# CAN-D_Rev1.net
KiCad netlist of a schematic drawn in EAGLE
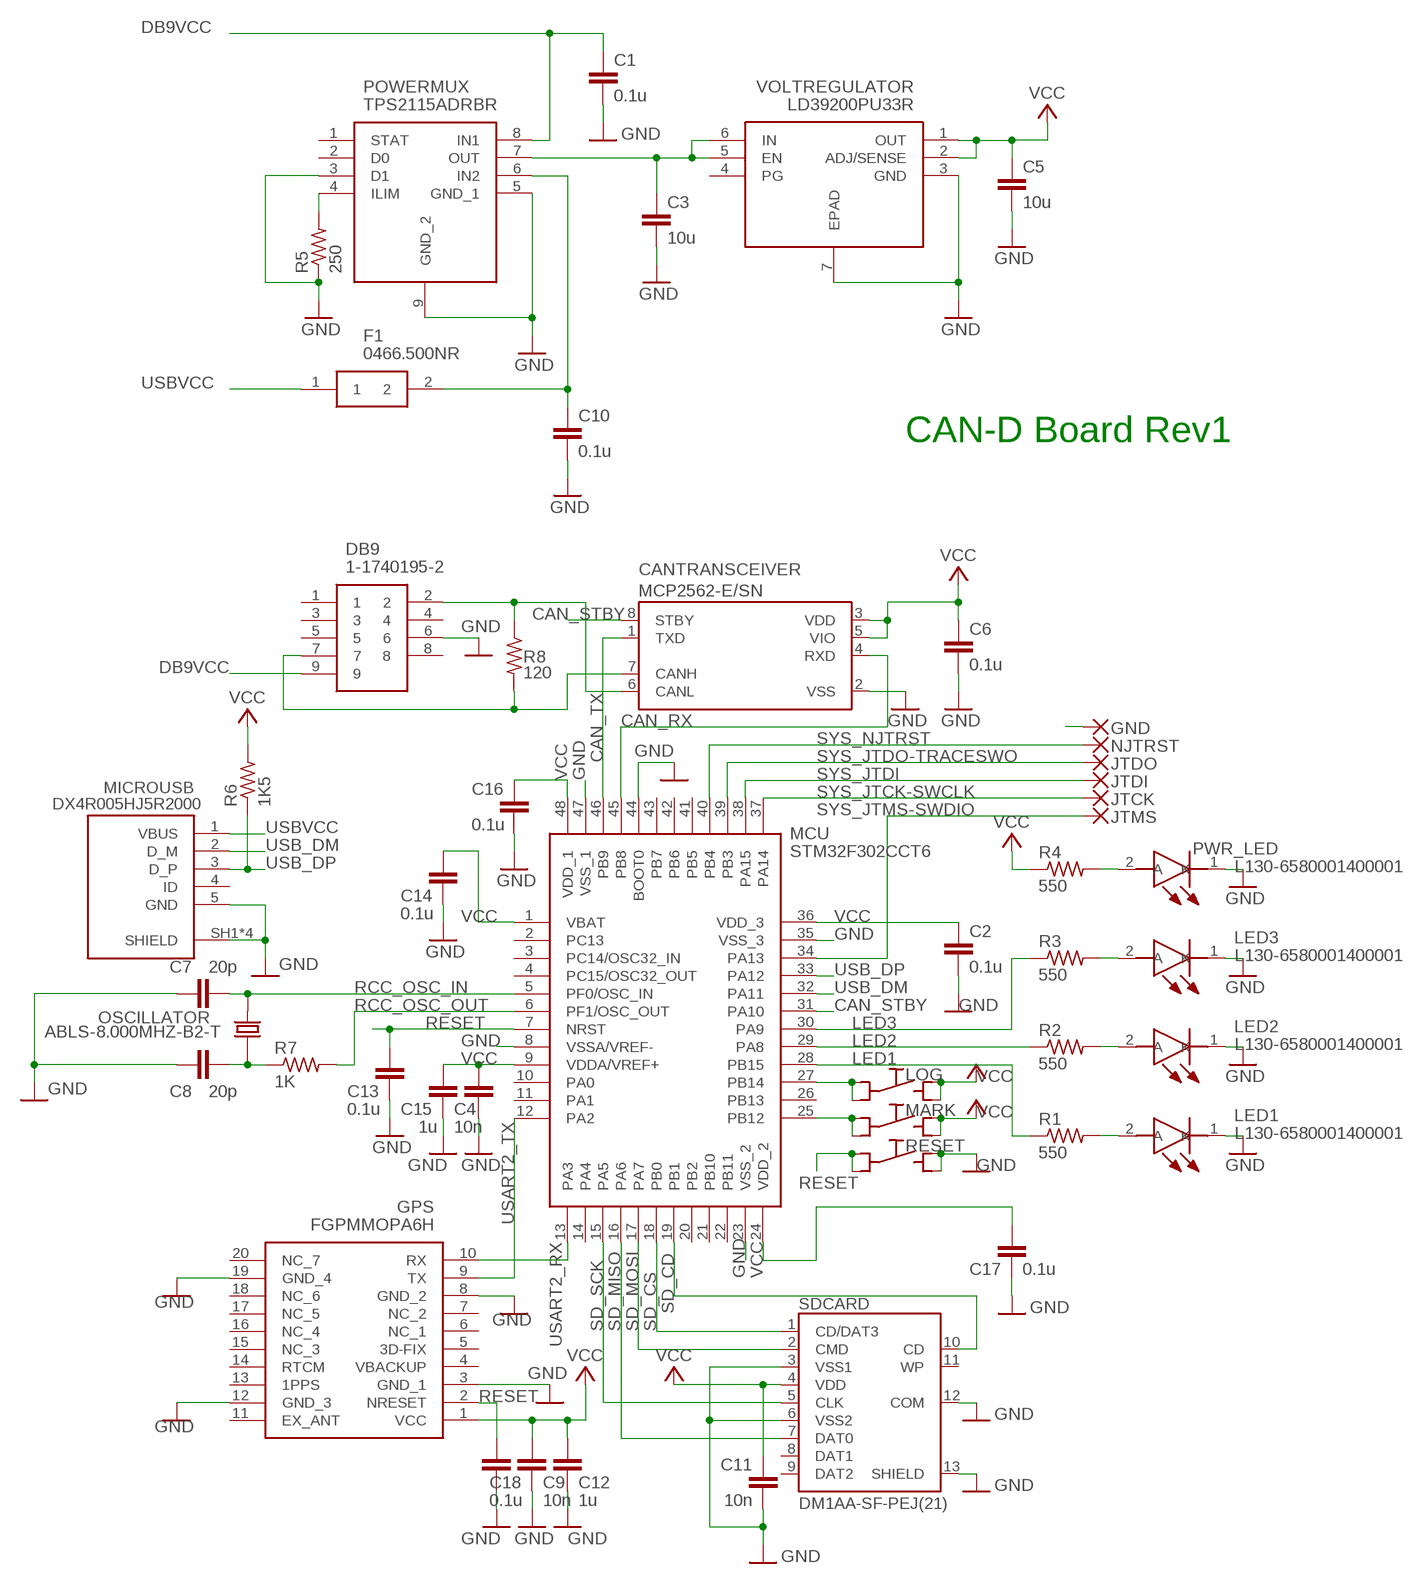
[diagram p0: schematic, sheet 1]

(export (version "E")
  (design (tool "Eeschema 10.0.6"))
  (components
    (comp (ref "C1")
      (value "0.1u")
      (footprint "eagle-import:C0603")
      (libsource (lib "eagle-import") (part "C-EUC0603"))
    )
    (comp (ref "C2")
      (value "0.1u")
      (footprint "eagle-import:C0603")
      (libsource (lib "eagle-import") (part "C-EUC0603"))
    )
    (comp (ref "C3")
      (value "10u")
      (footprint "eagle-import:C0603")
      (libsource (lib "eagle-import") (part "C-EUC0603"))
    )
    (comp (ref "C4")
      (value "10n")
      (footprint "eagle-import:C0603")
      (libsource (lib "eagle-import") (part "C-EUC0603"))
    )
    (comp (ref "C5")
      (value "10u")
      (footprint "eagle-import:C0603")
      (libsource (lib "eagle-import") (part "C-EUC0603"))
    )
    (comp (ref "C6")
      (value "0.1u")
      (footprint "eagle-import:C0603")
      (libsource (lib "eagle-import") (part "C-EUC0603"))
    )
    (comp (ref "C7")
      (value "20p")
      (footprint "eagle-import:C0603")
      (libsource (lib "eagle-import") (part "C-EUC0603"))
    )
    (comp (ref "C8")
      (value "20p")
      (footprint "eagle-import:C0603")
      (libsource (lib "eagle-import") (part "C-EUC0603"))
    )
    (comp (ref "C9")
      (value "10n")
      (footprint "eagle-import:C0603")
      (libsource (lib "eagle-import") (part "C-EUC0603"))
    )
    (comp (ref "C10")
      (value "0.1u")
      (footprint "eagle-import:C0603")
      (libsource (lib "eagle-import") (part "C-EUC0603"))
    )
    (comp (ref "C11")
      (value "10n")
      (footprint "eagle-import:C0603")
      (libsource (lib "eagle-import") (part "C-EUC0603"))
    )
    (comp (ref "C12")
      (value "1u")
      (footprint "eagle-import:C0603")
      (libsource (lib "eagle-import") (part "C-EUC0603"))
    )
    (comp (ref "C13")
      (value "0.1u")
      (footprint "eagle-import:C0603")
      (libsource (lib "eagle-import") (part "C-EUC0603"))
    )
    (comp (ref "C14")
      (value "0.1u")
      (footprint "eagle-import:C0603")
      (libsource (lib "eagle-import") (part "C-EUC0603"))
    )
    (comp (ref "C15")
      (value "1u")
      (footprint "eagle-import:C0603")
      (libsource (lib "eagle-import") (part "C-EUC0603"))
    )
    (comp (ref "C16")
      (value "0.1u")
      (footprint "eagle-import:C0603")
      (libsource (lib "eagle-import") (part "C-EUC0603"))
    )
    (comp (ref "C17")
      (value "0.1u")
      (footprint "eagle-import:C0603")
      (libsource (lib "eagle-import") (part "C-EUC0603"))
    )
    (comp (ref "C18")
      (value "0.1u")
      (footprint "eagle-import:C0603")
      (libsource (lib "eagle-import") (part "C-EUC0603"))
    )
    (comp (ref "CANTRANSCEIVER")
      (value "MCP2562-E/SN")
      (footprint "eagle-import:SOIC127P600X175-8N")
      (fields (field (name "MF") "Microchip"))
      (libsource (lib "eagle-import") (part "MCP2562-E/SN"))
    )
    (comp (ref "DB9")
      (value "1-1740195-2")
      (footprint "eagle-import:1-1740195-2")
      (fields
        (field (name "MOUSER_PART_NUMBER") "571-1-1740195-2")
        (field (name "RS_PART_NUMBER") "5269513P")
      )
      (libsource (lib "eagle-import") (part "1-1740195-2"))
    )
    (comp (ref "F1")
      (value "0466.500NR")
      (footprint "eagle-import:FUSC3215X58N")
      (fields (field (name "MOUSER_PART_NUMBER") "576-0466.500NR") (field (name "RS_PART_NUMBER") "5413568"))
      (libsource (lib "eagle-import") (part "0466.500NR"))
    )
    (comp (ref "GND")
      (value "2,54/1,1")
      (footprint "eagle-import:2,54_1,1")
      (libsource (lib "eagle-import") (part "2,54/1,1"))
    )
    (comp (ref "GPS")
      (value "FGPMMOPA6H")
      (footprint "eagle-import:FGPMMOPA6H")
      (libsource (lib "eagle-import") (part "FGPMMOPA6H"))
    )
    (comp (ref "JTCK")
      (value "2,54/1,1")
      (footprint "eagle-import:2,54_1,1")
      (libsource (lib "eagle-import") (part "2,54/1,1"))
    )
    (comp (ref "JTDI")
      (value "2,54/1,1")
      (footprint "eagle-import:2,54_1,1")
      (libsource (lib "eagle-import") (part "2,54/1,1"))
    )
    (comp (ref "JTDO")
      (value "2,54/1,1")
      (footprint "eagle-import:2,54_1,1")
      (libsource (lib "eagle-import") (part "2,54/1,1"))
    )
    (comp (ref "JTMS")
      (value "2,54/1,1")
      (footprint "eagle-import:2,54_1,1")
      (libsource (lib "eagle-import") (part "2,54/1,1"))
    )
    (comp (ref "LED1")
      (value "L130-6580001400001")
      (footprint "eagle-import:L130-6580001400001")
      (fields
        (field (name "MOUSER_PART_NUMBER") "997-L130-65800014001")
        (field (name "RS_PART_NUMBER") "1709867")
      )
      (libsource (lib "eagle-import") (part "L130-6580001400001"))
    )
    (comp (ref "LED2")
      (value "L130-6580001400001")
      (footprint "eagle-import:L130-6580001400001")
      (fields
        (field (name "MOUSER_PART_NUMBER") "997-L130-65800014001")
        (field (name "RS_PART_NUMBER") "1709867")
      )
      (libsource (lib "eagle-import") (part "L130-6580001400001"))
    )
    (comp (ref "LED3")
      (value "L130-6580001400001")
      (footprint "eagle-import:L130-6580001400001")
      (fields
        (field (name "MOUSER_PART_NUMBER") "997-L130-65800014001")
        (field (name "RS_PART_NUMBER") "1709867")
      )
      (libsource (lib "eagle-import") (part "L130-6580001400001"))
    )
    (comp (ref "LOG")
      (value "SCHURTER-LSH-1301.9314")
      (footprint "eagle-import:LSH")
      (libsource (lib "eagle-import") (part "SCHURTER-LSH-1301.9314"))
    )
    (comp (ref "MARK")
      (value "SCHURTER-LSH-1301.9314")
      (footprint "eagle-import:LSH")
      (libsource (lib "eagle-import") (part "SCHURTER-LSH-1301.9314"))
    )
    (comp (ref "MCU")
      (value "STM32F302CCT6")
      (footprint "eagle-import:QFP50P900X900X160-48N")
      (fields
        (field (name "MOUSER_PART_NUMBER") "511-STM32F302CCT6")
        (field (name "RS_PART_NUMBER") "1656736")
      )
      (libsource (lib "eagle-import") (part "STM32F302CCT6"))
    )
    (comp (ref "MICROUSB")
      (value "DX4R005HJ5R2000")
      (footprint "eagle-import:JAE_DX4R005HJ5R2000")
      (fields (field (name "DIGI-KEY_PART_NUMBER") "670-2674-1-ND") (field (name "MF") "JAE Electronics"))
      (libsource (lib "eagle-import") (part "DX4R005HJ5R2000"))
    )
    (comp (ref "NJTRST")
      (value "2,54/1,1")
      (footprint "eagle-import:2,54_1,1")
      (libsource (lib "eagle-import") (part "2,54/1,1"))
    )
    (comp (ref "OSCILLATOR")
      (value "ABLS-8.000MHZ-B2-T")
      (footprint "eagle-import:XTAL_ABLS-8.000MHZ-B2-T")
      (fields (field (name "MF") "Abracon LLC"))
      (libsource (lib "eagle-import") (part "ABLS-8.000MHZ-B2-T"))
    )
    (comp (ref "POWERMUX")
      (value "TPS2115ADRBR")
      (footprint "eagle-import:SON65P300X300X100-9N")
      (fields (field (name "MOUSER_PART_NUMBER") "595-TPS2115ADRBR"))
      (libsource (lib "eagle-import") (part "TPS2115ADRBR"))
    )
    (comp (ref "PWR_LED")
      (value "L130-6580001400001")
      (footprint "eagle-import:L130-6580001400001")
      (fields
        (field (name "MOUSER_PART_NUMBER") "997-L130-65800014001")
        (field (name "RS_PART_NUMBER") "1709867")
      )
      (libsource (lib "eagle-import") (part "L130-6580001400001"))
    )
    (comp (ref "R1")
      (value "550")
      (footprint "eagle-import:R0603")
      (libsource (lib "eagle-import") (part "R-US_R0603"))
    )
    (comp (ref "R2")
      (value "550")
      (footprint "eagle-import:R0603")
      (libsource (lib "eagle-import") (part "R-US_R0603"))
    )
    (comp (ref "R3")
      (value "550")
      (footprint "eagle-import:R0603")
      (libsource (lib "eagle-import") (part "R-US_R0603"))
    )
    (comp (ref "R4")
      (value "550")
      (footprint "eagle-import:R0603")
      (libsource (lib "eagle-import") (part "R-US_R0603"))
    )
    (comp (ref "R5")
      (value "250")
      (footprint "eagle-import:R0603")
      (libsource (lib "eagle-import") (part "R-US_R0603"))
    )
    (comp (ref "R6")
      (value "1K5")
      (footprint "eagle-import:R0603")
      (libsource (lib "eagle-import") (part "R-US_R0603"))
    )
    (comp (ref "R7")
      (value "1K")
      (footprint "eagle-import:R0603")
      (libsource (lib "eagle-import") (part "R-US_R0603"))
    )
    (comp (ref "R8")
      (value "120")
      (footprint "eagle-import:R0603")
      (libsource (lib "eagle-import") (part "R-US_R0603"))
    )
    (comp (ref "RESET")
      (value "SCHURTER-LSH-1301.9314")
      (footprint "eagle-import:LSH")
      (libsource (lib "eagle-import") (part "SCHURTER-LSH-1301.9314"))
    )
    (comp (ref "SDCARD")
      (value "DM1AA-SF-PEJ(21)")
      (footprint "eagle-import:HRS_DM1AA-SF-PEJ(21)")
      (fields
        (field (name "DIGI-KEY_PART_NUMBER") "HR845CT-ND")
        (field (name "MF") "Hirose")
        (field (name "MP") "DM1AA-SF-PEJ_21_")
      )
      (libsource (lib "eagle-import") (part "DM1AA-SF-PEJ(21)"))
    )
    (comp (ref "VOLTREGULATOR")
      (value "LD39200PU33R")
      (footprint "eagle-import:SON95P300X300X100-7N")
      (fields (field (name "MOUSER_PART_NUMBER") "511-LD39200PU33R"))
      (libsource (lib "eagle-import") (part "LD39200PU33R"))
    )
  )
  (nets
    (net (code "1") (name "/CAN_RX") (class "Default")
      (node (ref "CANTRANSCEIVER") (pin "4") (pinfunction "RXD_4") (pintype "output"))
      (node (ref "MCU") (pin "45") (pinfunction "PB8_45") (pintype "bidirectional"))
    )
    (net (code "2") (name "/CAN_STBY") (class "Default")
      (node (ref "CANTRANSCEIVER") (pin "8") (pinfunction "STBY_8") (pintype "input"))
      (node (ref "MCU") (pin "31") (pinfunction "PA10_31") (pintype "bidirectional"))
    )
    (net (code "3") (name "/CAN_TX") (class "Default")
      (node (ref "CANTRANSCEIVER") (pin "1") (pinfunction "TXD_1") (pintype "input"))
      (node (ref "MCU") (pin "46") (pinfunction "PB9_46") (pintype "bidirectional"))
    )
    (net (code "4") (name "/DB9VCC") (class "Default")
      (node (ref "C1") (pin "1") (pinfunction "1_1") (pintype "passive"))
      (node (ref "DB9") (pin "9") (pinfunction "9_9") (pintype "bidirectional"))
      (node (ref "POWERMUX") (pin "8") (pinfunction "IN1_8") (pintype "bidirectional"))
    )
    (net (code "5") (name "/LED1") (class "Default")
      (node (ref "MCU") (pin "28") (pinfunction "PB15_28") (pintype "bidirectional"))
      (node (ref "R1") (pin "1") (pinfunction "1_1") (pintype "passive"))
    )
    (net (code "6") (name "/LED2") (class "Default")
      (node (ref "MCU") (pin "29") (pinfunction "PA8_29") (pintype "bidirectional"))
      (node (ref "R2") (pin "1") (pinfunction "1_1") (pintype "passive"))
    )
    (net (code "7") (name "/LED3") (class "Default")
      (node (ref "MCU") (pin "30") (pinfunction "PA9_30") (pintype "bidirectional"))
      (node (ref "R3") (pin "1") (pinfunction "1_1") (pintype "passive"))
    )
    (net (code "8") (name "/RCC_OSC_IN") (class "Default")
      (node (ref "C7") (pin "1") (pinfunction "1_1") (pintype "passive"))
      (node (ref "MCU") (pin "5") (pinfunction "PF0/OSC_IN_5") (pintype "input"))
      (node (ref "OSCILLATOR") (pin "2") (pinfunction "2_2") (pintype "passive"))
    )
    (net (code "9") (name "/RCC_OSC_OUT") (class "Default")
      (node (ref "MCU") (pin "6") (pinfunction "PF1/OSC_OUT_6") (pintype "output"))
      (node (ref "R7") (pin "2") (pinfunction "2_2") (pintype "passive"))
    )
    (net (code "10") (name "/RESET") (class "Default")
      (node (ref "C13") (pin "1") (pinfunction "1_1") (pintype "passive"))
      (node (ref "C18") (pin "1") (pinfunction "1_1") (pintype "passive"))
      (node (ref "GPS") (pin "2") (pinfunction "NRESET_2") (pintype "bidirectional"))
      (node (ref "MCU") (pin "7") (pinfunction "NRST_7") (pintype "input"))
      (node (ref "RESET") (pin "C1") (pinfunction "C_C1") (pintype "passive"))
      (node (ref "RESET") (pin "C2") (pinfunction "C_C2") (pintype "passive"))
    )
    (net (code "11") (name "/SD_CD") (class "Default")
      (node (ref "MCU") (pin "19") (pinfunction "PB1_19") (pintype "bidirectional"))
      (node (ref "SDCARD") (pin "10") (pinfunction "CD_10") (pintype "passive"))
    )
    (net (code "12") (name "/SD_CS") (class "Default")
      (node (ref "MCU") (pin "18") (pinfunction "PB0_18") (pintype "bidirectional"))
      (node (ref "SDCARD") (pin "1") (pinfunction "CD/DAT3_1") (pintype "bidirectional"))
    )
    (net (code "13") (name "/SD_MISO") (class "Default")
      (node (ref "MCU") (pin "16") (pinfunction "PA6_16") (pintype "bidirectional"))
      (node (ref "SDCARD") (pin "7") (pinfunction "DAT0_7") (pintype "bidirectional"))
    )
    (net (code "14") (name "/SD_MOSI") (class "Default")
      (node (ref "MCU") (pin "17") (pinfunction "PA7_17") (pintype "bidirectional"))
      (node (ref "SDCARD") (pin "2") (pinfunction "CMD_2") (pintype "bidirectional"))
    )
    (net (code "15") (name "/SD_SCK") (class "Default")
      (node (ref "MCU") (pin "15") (pinfunction "PA5_15") (pintype "bidirectional"))
      (node (ref "SDCARD") (pin "5") (pinfunction "CLK_5") (pintype "bidirectional"))
    )
    (net (code "16") (name "/SYS_JTCK-SWCLK") (class "Default")
      (node (ref "JTCK") (pin "1") (pinfunction "P_1") (pintype "passive"))
      (node (ref "MCU") (pin "37") (pinfunction "PA14_37") (pintype "bidirectional"))
    )
    (net (code "17") (name "/SYS_JTDI") (class "Default")
      (node (ref "JTDI") (pin "1") (pinfunction "P_1") (pintype "passive"))
      (node (ref "MCU") (pin "38") (pinfunction "PA15_38") (pintype "bidirectional"))
    )
    (net (code "18") (name "/SYS_JTDO-TRACESWO") (class "Default")
      (node (ref "JTDO") (pin "1") (pinfunction "P_1") (pintype "passive"))
      (node (ref "MCU") (pin "39") (pinfunction "PB3_39") (pintype "bidirectional"))
    )
    (net (code "19") (name "/SYS_JTMS-SWDIO") (class "Default")
      (node (ref "JTMS") (pin "1") (pinfunction "P_1") (pintype "passive"))
      (node (ref "MCU") (pin "34") (pinfunction "PA13_34") (pintype "bidirectional"))
    )
    (net (code "20") (name "/SYS_NJTRST") (class "Default")
      (node (ref "MCU") (pin "40") (pinfunction "PB4_40") (pintype "bidirectional"))
      (node (ref "NJTRST") (pin "1") (pinfunction "P_1") (pintype "passive"))
    )
    (net (code "21") (name "/USART2_RX") (class "Default")
      (node (ref "GPS") (pin "10") (pinfunction "RX_10") (pintype "bidirectional"))
      (node (ref "MCU") (pin "13") (pinfunction "PA3_13") (pintype "bidirectional"))
    )
    (net (code "22") (name "/USART2_TX") (class "Default")
      (node (ref "GPS") (pin "9") (pinfunction "TX_9") (pintype "bidirectional"))
      (node (ref "MCU") (pin "12") (pinfunction "PA2_12") (pintype "bidirectional"))
    )
    (net (code "23") (name "/USBVCC") (class "Default")
      (node (ref "F1") (pin "1") (pinfunction "1_1") (pintype "bidirectional"))
      (node (ref "MICROUSB") (pin "1") (pinfunction "VBUS_1") (pintype "passive"))
    )
    (net (code "24") (name "/USB_DM") (class "Default")
      (node (ref "MCU") (pin "32") (pinfunction "PA11_32") (pintype "bidirectional"))
      (node (ref "MICROUSB") (pin "2") (pinfunction "D_M_2") (pintype "passive"))
    )
    (net (code "25") (name "/USB_DP") (class "Default")
      (node (ref "MCU") (pin "33") (pinfunction "PA12_33") (pintype "bidirectional"))
      (node (ref "MICROUSB") (pin "3") (pinfunction "D_P_3") (pintype "passive"))
      (node (ref "R6") (pin "1") (pinfunction "1_1") (pintype "passive"))
    )
    (net (code "26") (name "GND") (class "Default")
      (node (ref "C1") (pin "2") (pinfunction "2_2") (pintype "passive"))
      (node (ref "C10") (pin "2") (pinfunction "2_2") (pintype "passive"))
      (node (ref "C11") (pin "2") (pinfunction "2_2") (pintype "passive"))
      (node (ref "C12") (pin "2") (pinfunction "2_2") (pintype "passive"))
      (node (ref "C13") (pin "2") (pinfunction "2_2") (pintype "passive"))
      (node (ref "C14") (pin "2") (pinfunction "2_2") (pintype "passive"))
      (node (ref "C15") (pin "2") (pinfunction "2_2") (pintype "passive"))
      (node (ref "C16") (pin "2") (pinfunction "2_2") (pintype "passive"))
      (node (ref "C17") (pin "2") (pinfunction "2_2") (pintype "passive"))
      (node (ref "C18") (pin "2") (pinfunction "2_2") (pintype "passive"))
      (node (ref "C2") (pin "2") (pinfunction "2_2") (pintype "passive"))
      (node (ref "C3") (pin "2") (pinfunction "2_2") (pintype "passive"))
      (node (ref "C4") (pin "2") (pinfunction "2_2") (pintype "passive"))
      (node (ref "C5") (pin "2") (pinfunction "2_2") (pintype "passive"))
      (node (ref "C6") (pin "2") (pinfunction "2_2") (pintype "passive"))
      (node (ref "C7") (pin "2") (pinfunction "2_2") (pintype "passive"))
      (node (ref "C8") (pin "2") (pinfunction "2_2") (pintype "passive"))
      (node (ref "C9") (pin "2") (pinfunction "2_2") (pintype "passive"))
      (node (ref "CANTRANSCEIVER") (pin "2") (pinfunction "VSS_2") (pintype "power_in"))
      (node (ref "DB9") (pin "6") (pinfunction "6_6") (pintype "bidirectional"))
      (node (ref "GND") (pin "1") (pinfunction "P_1") (pintype "passive"))
      (node (ref "GPS") (pin "12") (pinfunction "GND_3_12") (pintype "bidirectional"))
      (node (ref "GPS") (pin "19") (pinfunction "GND_4_19") (pintype "bidirectional"))
      (node (ref "GPS") (pin "3") (pinfunction "GND_1_3") (pintype "bidirectional"))
      (node (ref "GPS") (pin "8") (pinfunction "GND_2_8") (pintype "bidirectional"))
      (node (ref "LED1") (pin "1") (pinfunction "K_1") (pintype "bidirectional"))
      (node (ref "LED2") (pin "1") (pinfunction "K_1") (pintype "bidirectional"))
      (node (ref "LED3") (pin "1") (pinfunction "K_1") (pintype "bidirectional"))
      (node (ref "MCU") (pin "23") (pinfunction "VSS_2_23") (pintype "power_in"))
      (node (ref "MCU") (pin "35") (pinfunction "VSS_3_35") (pintype "power_in"))
      (node (ref "MCU") (pin "44") (pinfunction "BOOT0_44") (pintype "bidirectional"))
      (node (ref "MCU") (pin "47") (pinfunction "VSS_1_47") (pintype "power_in"))
      (node (ref "MCU") (pin "8") (pinfunction "VSSA/VREF-_8") (pintype "power_in"))
      (node (ref "MICROUSB") (pin "5") (pinfunction "GND_5") (pintype "passive"))
      (node (ref "MICROUSB") (pin "SH1") (pinfunction "SHIELD_SH1") (pintype "passive"))
      (node (ref "MICROUSB") (pin "SH2") (pinfunction "SHIELD_SH2") (pintype "passive"))
      (node (ref "MICROUSB") (pin "SH3") (pinfunction "SHIELD_SH3") (pintype "passive"))
      (node (ref "MICROUSB") (pin "SH4") (pinfunction "SHIELD_SH4") (pintype "passive"))
      (node (ref "POWERMUX") (pin "3") (pinfunction "D1_3") (pintype "bidirectional"))
      (node (ref "POWERMUX") (pin "5") (pinfunction "GND_1_5") (pintype "bidirectional"))
      (node (ref "POWERMUX") (pin "9") (pinfunction "GND_2_9") (pintype "bidirectional"))
      (node (ref "PWR_LED") (pin "1") (pinfunction "K_1") (pintype "bidirectional"))
      (node (ref "R5") (pin "1") (pinfunction "1_1") (pintype "passive"))
      (node (ref "RESET") (pin "NO1") (pinfunction "NO_NO1") (pintype "passive"))
      (node (ref "RESET") (pin "NO2") (pinfunction "NO_NO2") (pintype "passive"))
      (node (ref "SDCARD") (pin "12") (pinfunction "COM_12") (pintype "passive"))
      (node (ref "SDCARD") (pin "13") (pinfunction "SHIELD_13") (pintype "passive"))
      (node (ref "SDCARD") (pin "3") (pinfunction "VSS1_3") (pintype "power_in"))
      (node (ref "SDCARD") (pin "6") (pinfunction "VSS2_6") (pintype "power_in"))
      (node (ref "VOLTREGULATOR") (pin "3") (pinfunction "GND_3") (pintype "bidirectional"))
      (node (ref "VOLTREGULATOR") (pin "7") (pinfunction "EPAD_7") (pintype "bidirectional"))
    )
    (net (code "27") (name "Net-(C8-Pad1)") (class "Default")
      (node (ref "C8") (pin "1") (pinfunction "1_1") (pintype "passive"))
      (node (ref "OSCILLATOR") (pin "1") (pinfunction "1_1") (pintype "passive"))
      (node (ref "R7") (pin "1") (pinfunction "1_1") (pintype "passive"))
    )
    (net (code "28") (name "Net-(CANTRANSCEIVER-CANH)") (class "Default")
      (node (ref "CANTRANSCEIVER") (pin "7") (pinfunction "CANH_7") (pintype "input"))
      (node (ref "DB9") (pin "7") (pinfunction "7_7") (pintype "bidirectional"))
      (node (ref "R8") (pin "2") (pinfunction "2_2") (pintype "passive"))
    )
    (net (code "29") (name "Net-(CANTRANSCEIVER-CANL)") (class "Default")
      (node (ref "CANTRANSCEIVER") (pin "6") (pinfunction "CANL_6") (pintype "input"))
      (node (ref "DB9") (pin "2") (pinfunction "2_2") (pintype "bidirectional"))
      (node (ref "R8") (pin "1") (pinfunction "1_1") (pintype "passive"))
    )
    (net (code "30") (name "Net-(LED1-A)") (class "Default")
      (node (ref "LED1") (pin "2") (pinfunction "A_2") (pintype "bidirectional"))
      (node (ref "R1") (pin "2") (pinfunction "2_2") (pintype "passive"))
    )
    (net (code "31") (name "Net-(LED2-A)") (class "Default")
      (node (ref "LED2") (pin "2") (pinfunction "A_2") (pintype "bidirectional"))
      (node (ref "R2") (pin "2") (pinfunction "2_2") (pintype "passive"))
    )
    (net (code "32") (name "Net-(LED3-A)") (class "Default")
      (node (ref "LED3") (pin "2") (pinfunction "A_2") (pintype "bidirectional"))
      (node (ref "R3") (pin "2") (pinfunction "2_2") (pintype "passive"))
    )
    (net (code "33") (name "Net-(MCU-PB12)") (class "Default")
      (node (ref "MARK") (pin "C1") (pinfunction "C_C1") (pintype "passive"))
      (node (ref "MARK") (pin "C2") (pinfunction "C_C2") (pintype "passive"))
      (node (ref "MCU") (pin "25") (pinfunction "PB12_25") (pintype "bidirectional"))
    )
    (net (code "34") (name "Net-(MCU-PB14)") (class "Default")
      (node (ref "LOG") (pin "C1") (pinfunction "C_C1") (pintype "passive"))
      (node (ref "LOG") (pin "C2") (pinfunction "C_C2") (pintype "passive"))
      (node (ref "MCU") (pin "27") (pinfunction "PB14_27") (pintype "bidirectional"))
    )
    (net (code "35") (name "Net-(POWERMUX-ILIM)") (class "Default")
      (node (ref "POWERMUX") (pin "4") (pinfunction "ILIM_4") (pintype "bidirectional"))
      (node (ref "R5") (pin "2") (pinfunction "2_2") (pintype "passive"))
    )
    (net (code "36") (name "Net-(POWERMUX-IN2)") (class "Default")
      (node (ref "C10") (pin "1") (pinfunction "1_1") (pintype "passive"))
      (node (ref "F1") (pin "2") (pinfunction "2_2") (pintype "bidirectional"))
      (node (ref "POWERMUX") (pin "6") (pinfunction "IN2_6") (pintype "bidirectional"))
    )
    (net (code "37") (name "Net-(POWERMUX-OUT)") (class "Default")
      (node (ref "C3") (pin "1") (pinfunction "1_1") (pintype "passive"))
      (node (ref "POWERMUX") (pin "7") (pinfunction "OUT_7") (pintype "bidirectional"))
      (node (ref "VOLTREGULATOR") (pin "5") (pinfunction "EN_5") (pintype "bidirectional"))
      (node (ref "VOLTREGULATOR") (pin "6") (pinfunction "IN_6") (pintype "bidirectional"))
    )
    (net (code "38") (name "Net-(PWR_LED-A)") (class "Default")
      (node (ref "PWR_LED") (pin "2") (pinfunction "A_2") (pintype "bidirectional"))
      (node (ref "R4") (pin "2") (pinfunction "2_2") (pintype "passive"))
    )
    (net (code "39") (name "VCC") (class "Default")
      (node (ref "C11") (pin "1") (pinfunction "1_1") (pintype "passive"))
      (node (ref "C12") (pin "1") (pinfunction "1_1") (pintype "passive"))
      (node (ref "C14") (pin "1") (pinfunction "1_1") (pintype "passive"))
      (node (ref "C15") (pin "1") (pinfunction "1_1") (pintype "passive"))
      (node (ref "C16") (pin "1") (pinfunction "1_1") (pintype "passive"))
      (node (ref "C17") (pin "1") (pinfunction "1_1") (pintype "passive"))
      (node (ref "C2") (pin "1") (pinfunction "1_1") (pintype "passive"))
      (node (ref "C4") (pin "1") (pinfunction "1_1") (pintype "passive"))
      (node (ref "C5") (pin "1") (pinfunction "1_1") (pintype "passive"))
      (node (ref "C6") (pin "1") (pinfunction "1_1") (pintype "passive"))
      (node (ref "C9") (pin "1") (pinfunction "1_1") (pintype "passive"))
      (node (ref "CANTRANSCEIVER") (pin "3") (pinfunction "VDD_3") (pintype "power_in"))
      (node (ref "CANTRANSCEIVER") (pin "5") (pinfunction "VIO_5") (pintype "power_in"))
      (node (ref "GPS") (pin "1") (pinfunction "VCC_1") (pintype "bidirectional"))
      (node (ref "LOG") (pin "NO1") (pinfunction "NO_NO1") (pintype "passive"))
      (node (ref "LOG") (pin "NO2") (pinfunction "NO_NO2") (pintype "passive"))
      (node (ref "MARK") (pin "NO1") (pinfunction "NO_NO1") (pintype "passive"))
      (node (ref "MARK") (pin "NO2") (pinfunction "NO_NO2") (pintype "passive"))
      (node (ref "MCU") (pin "1") (pinfunction "VBAT_1") (pintype "bidirectional"))
      (node (ref "MCU") (pin "24") (pinfunction "VDD_2_24") (pintype "power_in"))
      (node (ref "MCU") (pin "36") (pinfunction "VDD_3_36") (pintype "power_in"))
      (node (ref "MCU") (pin "48") (pinfunction "VDD_1_48") (pintype "power_in"))
      (node (ref "MCU") (pin "9") (pinfunction "VDDA/VREF+_9") (pintype "power_in"))
      (node (ref "R4") (pin "1") (pinfunction "1_1") (pintype "passive"))
      (node (ref "R6") (pin "2") (pinfunction "2_2") (pintype "passive"))
      (node (ref "SDCARD") (pin "4") (pinfunction "VDD_4") (pintype "power_in"))
      (node (ref "VOLTREGULATOR") (pin "1") (pinfunction "OUT_1") (pintype "bidirectional"))
      (node (ref "VOLTREGULATOR") (pin "2") (pinfunction "ADJ/SENSE_2") (pintype "bidirectional"))
    )
    (net (code "40") (name "unconnected-(DB9-Pad1)") (class "Default")
      (node (ref "DB9") (pin "1") (pinfunction "1_1") (pintype "bidirectional"))
    )
    (net (code "41") (name "unconnected-(DB9-Pad3)") (class "Default")
      (node (ref "DB9") (pin "3") (pinfunction "3_3") (pintype "bidirectional"))
    )
    (net (code "42") (name "unconnected-(DB9-Pad4)") (class "Default")
      (node (ref "DB9") (pin "4") (pinfunction "4_4") (pintype "bidirectional"))
    )
    (net (code "43") (name "unconnected-(DB9-Pad5)") (class "Default")
      (node (ref "DB9") (pin "5") (pinfunction "5_5") (pintype "bidirectional"))
    )
    (net (code "44") (name "unconnected-(DB9-Pad8)") (class "Default")
      (node (ref "DB9") (pin "8") (pinfunction "8_8") (pintype "bidirectional"))
    )
    (net (code "45") (name "unconnected-(GPS-1PPS-Pad13)") (class "Default")
      (node (ref "GPS") (pin "13") (pinfunction "1PPS_13") (pintype "bidirectional"))
    )
    (net (code "46") (name "unconnected-(GPS-3D-FIX-Pad5)") (class "Default")
      (node (ref "GPS") (pin "5") (pinfunction "3D-FIX_5") (pintype "bidirectional"))
    )
    (net (code "47") (name "unconnected-(GPS-EX_ANT-Pad11)") (class "Default")
      (node (ref "GPS") (pin "11") (pinfunction "EX_ANT_11") (pintype "bidirectional"))
    )
    (net (code "48") (name "unconnected-(GPS-NC_1-Pad6)") (class "Default")
      (node (ref "GPS") (pin "6") (pinfunction "NC_1_6") (pintype "bidirectional"))
    )
    (net (code "49") (name "unconnected-(GPS-NC_2-Pad7)") (class "Default")
      (node (ref "GPS") (pin "7") (pinfunction "NC_2_7") (pintype "bidirectional"))
    )
    (net (code "50") (name "unconnected-(GPS-NC_3-Pad15)") (class "Default")
      (node (ref "GPS") (pin "15") (pinfunction "NC_3_15") (pintype "bidirectional"))
    )
    (net (code "51") (name "unconnected-(GPS-NC_4-Pad16)") (class "Default")
      (node (ref "GPS") (pin "16") (pinfunction "NC_4_16") (pintype "bidirectional"))
    )
    (net (code "52") (name "unconnected-(GPS-NC_5-Pad17)") (class "Default")
      (node (ref "GPS") (pin "17") (pinfunction "NC_5_17") (pintype "bidirectional"))
    )
    (net (code "53") (name "unconnected-(GPS-NC_6-Pad18)") (class "Default")
      (node (ref "GPS") (pin "18") (pinfunction "NC_6_18") (pintype "bidirectional"))
    )
    (net (code "54") (name "unconnected-(GPS-NC_7-Pad20)") (class "Default")
      (node (ref "GPS") (pin "20") (pinfunction "NC_7_20") (pintype "bidirectional"))
    )
    (net (code "55") (name "unconnected-(GPS-RTCM-Pad14)") (class "Default")
      (node (ref "GPS") (pin "14") (pinfunction "RTCM_14") (pintype "bidirectional"))
    )
    (net (code "56") (name "unconnected-(GPS-VBACKUP-Pad4)") (class "Default")
      (node (ref "GPS") (pin "4") (pinfunction "VBACKUP_4") (pintype "bidirectional"))
    )
    (net (code "57") (name "unconnected-(MCU-PA0-Pad10)") (class "Default")
      (node (ref "MCU") (pin "10") (pinfunction "PA0_10") (pintype "bidirectional"))
    )
    (net (code "58") (name "unconnected-(MCU-PA1-Pad11)") (class "Default")
      (node (ref "MCU") (pin "11") (pinfunction "PA1_11") (pintype "bidirectional"))
    )
    (net (code "59") (name "unconnected-(MCU-PA4-Pad14)") (class "Default")
      (node (ref "MCU") (pin "14") (pinfunction "PA4_14") (pintype "bidirectional"))
    )
    (net (code "60") (name "unconnected-(MCU-PB2-Pad20)") (class "Default")
      (node (ref "MCU") (pin "20") (pinfunction "PB2_20") (pintype "bidirectional"))
    )
    (net (code "61") (name "unconnected-(MCU-PB5-Pad41)") (class "Default")
      (node (ref "MCU") (pin "41") (pinfunction "PB5_41") (pintype "bidirectional"))
    )
    (net (code "62") (name "unconnected-(MCU-PB6-Pad42)") (class "Default")
      (node (ref "MCU") (pin "42") (pinfunction "PB6_42") (pintype "bidirectional"))
    )
    (net (code "63") (name "unconnected-(MCU-PB7-Pad43)") (class "Default")
      (node (ref "MCU") (pin "43") (pinfunction "PB7_43") (pintype "bidirectional"))
    )
    (net (code "64") (name "unconnected-(MCU-PB10-Pad21)") (class "Default")
      (node (ref "MCU") (pin "21") (pinfunction "PB10_21") (pintype "bidirectional"))
    )
    (net (code "65") (name "unconnected-(MCU-PB11-Pad22)") (class "Default")
      (node (ref "MCU") (pin "22") (pinfunction "PB11_22") (pintype "bidirectional"))
    )
    (net (code "66") (name "unconnected-(MCU-PB13-Pad26)") (class "Default")
      (node (ref "MCU") (pin "26") (pinfunction "PB13_26") (pintype "bidirectional"))
    )
    (net (code "67") (name "unconnected-(MCU-PC13-Pad2)") (class "Default")
      (node (ref "MCU") (pin "2") (pinfunction "PC13_2") (pintype "bidirectional"))
    )
    (net (code "68") (name "unconnected-(MCU-PC14{slash}OSC32_IN-Pad3)") (class "Default")
      (node (ref "MCU") (pin "3") (pinfunction "PC14/OSC32_IN_3") (pintype "input"))
    )
    (net (code "69") (name "unconnected-(MCU-PC15{slash}OSC32_OUT-Pad4)") (class "Default")
      (node (ref "MCU") (pin "4") (pinfunction "PC15/OSC32_OUT_4") (pintype "output"))
    )
    (net (code "70") (name "unconnected-(MICROUSB-ID-Pad4)") (class "Default")
      (node (ref "MICROUSB") (pin "4") (pinfunction "ID_4") (pintype "passive"))
    )
    (net (code "71") (name "unconnected-(POWERMUX-D0-Pad2)") (class "Default")
      (node (ref "POWERMUX") (pin "2") (pinfunction "D0_2") (pintype "bidirectional"))
    )
    (net (code "72") (name "unconnected-(POWERMUX-STAT-Pad1)") (class "Default")
      (node (ref "POWERMUX") (pin "1") (pinfunction "STAT_1") (pintype "bidirectional"))
    )
    (net (code "73") (name "unconnected-(SDCARD-DAT1-Pad8)") (class "Default")
      (node (ref "SDCARD") (pin "8") (pinfunction "DAT1_8") (pintype "bidirectional"))
    )
    (net (code "74") (name "unconnected-(SDCARD-DAT2-Pad9)") (class "Default")
      (node (ref "SDCARD") (pin "9") (pinfunction "DAT2_9") (pintype "bidirectional"))
    )
    (net (code "75") (name "unconnected-(SDCARD-WP-Pad11)") (class "Default")
      (node (ref "SDCARD") (pin "11") (pinfunction "WP_11") (pintype "passive"))
    )
    (net (code "76") (name "unconnected-(VOLTREGULATOR-PG-Pad4)") (class "Default")
      (node (ref "VOLTREGULATOR") (pin "4") (pinfunction "PG_4") (pintype "bidirectional"))
    )
  )
)
